# NSE2020_2.net
KiCad netlist of a schematic drawn in EAGLE
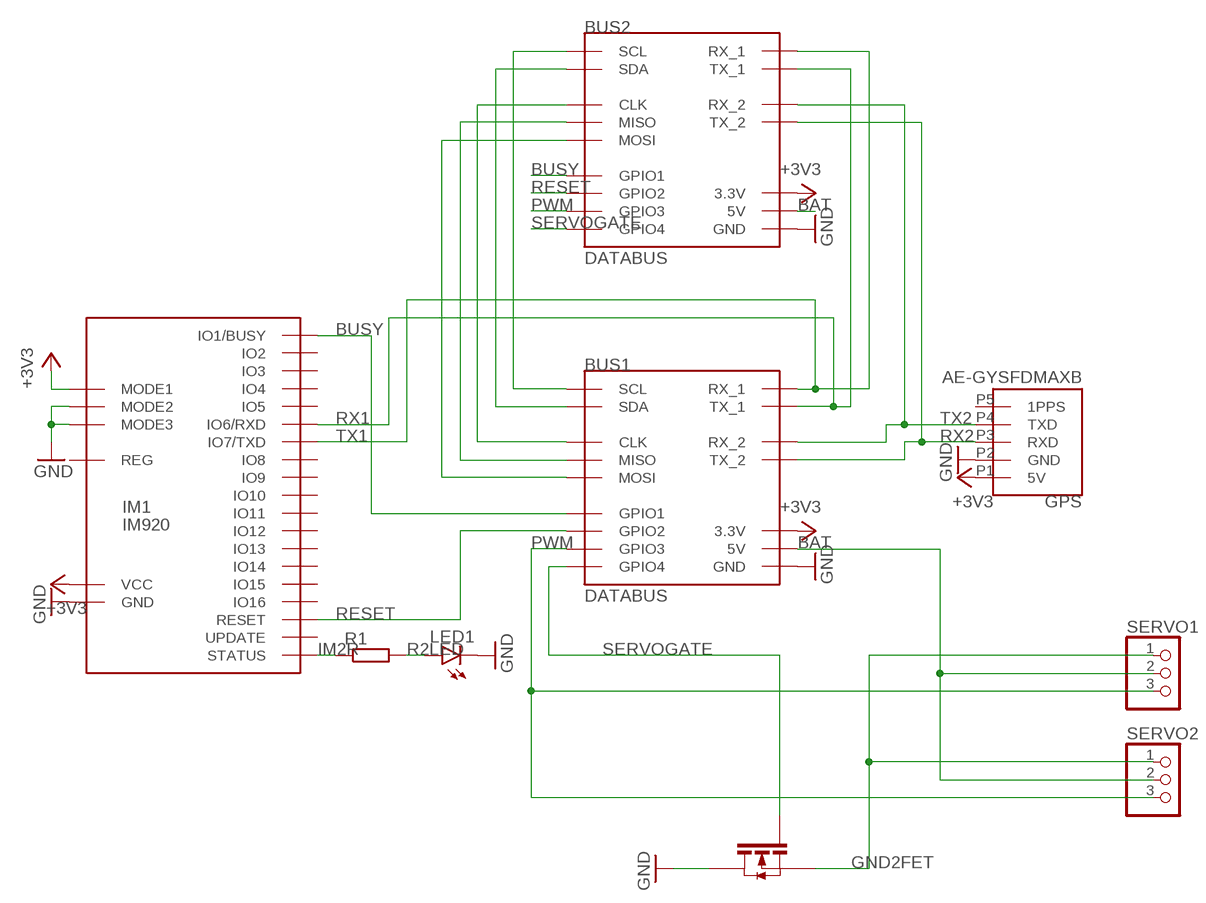
[diagram p0: schematic, sheet 1]

(export (version "E")
  (design (tool "Eeschema 10.0.6"))
  (components
    (comp (ref "BUS1")
      (value "DATABUS")
      (footprint "eagle-import:8X2")
      (libsource (lib "eagle-import") (part "DATABUS"))
    )
    (comp (ref "BUS2")
      (value "DATABUS")
      (footprint "eagle-import:8X2")
      (libsource (lib "eagle-import") (part "DATABUS"))
    )
    (comp (ref "FET1")
      (value "2SK4033")
      (footprint "eagle-import:2SK4033")
      (libsource (lib "eagle-import") (part "2SK4033"))
    )
    (comp (ref "GPS")
      (value "AE-GYSFDMAXB")
      (footprint "eagle-import:AE-GYSFDMAXB")
      (libsource (lib "eagle-import") (part "AE-GYSFDMAXB"))
    )
    (comp (ref "IM1")
      (value "IM920")
      (footprint "eagle-import:IM920")
      (libsource (lib "eagle-import") (part "IM920"))
    )
    (comp (ref "LED1")
      (value "LEDSMT1206")
      (footprint "eagle-import:1206")
      (libsource (lib "eagle-import") (part "LEDSMT1206"))
    )
    (comp (ref "R1")
      (value "R-EU_M2012")
      (footprint "eagle-import:M2012")
      (libsource (lib "eagle-import") (part "R-EU_M2012"))
    )
    (comp (ref "SERVO1")
      (value "PINHD-1X3")
      (footprint "eagle-import:1X03")
      (libsource (lib "eagle-import") (part "PINHD-1X3"))
    )
    (comp (ref "SERVO2")
      (value "PINHD-1X3")
      (footprint "eagle-import:1X03")
      (libsource (lib "eagle-import") (part "PINHD-1X3"))
    )
  )
  (nets
    (net (code "1") (name "+3V3") (class "Default")
      (node (ref "BUS1") (pin "P6") (pinfunction "3.3V_P6") (pintype "bidirectional"))
      (node (ref "BUS2") (pin "P6") (pinfunction "3.3V_P6") (pintype "bidirectional"))
      (node (ref "GPS") (pin "P1") (pinfunction "5V_P1") (pintype "bidirectional"))
      (node (ref "IM1") (pin "IO2") (pinfunction "VCC_IO2") (pintype "bidirectional"))
      (node (ref "IM1") (pin "IO5") (pinfunction "MODE1_IO5") (pintype "bidirectional"))
    )
    (net (code "2") (name "/BAT") (class "Default")
      (node (ref "BUS1") (pin "P7") (pinfunction "5V_P7") (pintype "bidirectional"))
      (node (ref "BUS2") (pin "P7") (pinfunction "5V_P7") (pintype "bidirectional"))
      (node (ref "SERVO1") (pin "2") (pinfunction "2_2") (pintype "passive"))
      (node (ref "SERVO2") (pin "2") (pinfunction "2_2") (pintype "passive"))
    )
    (net (code "3") (name "/BUSY") (class "Default")
      (node (ref "BUS1") (pin "P3") (pinfunction "GPIO1_P3") (pintype "bidirectional"))
      (node (ref "BUS2") (pin "P3") (pinfunction "GPIO1_P3") (pintype "bidirectional"))
      (node (ref "IM1") (pin "IO13") (pinfunction "IO1/BUSY_IO13") (pintype "bidirectional"))
    )
    (net (code "4") (name "/GND2FET") (class "Default")
      (node (ref "FET1") (pin "P$4") (pinfunction "S_P$4") (pintype "bidirectional"))
      (node (ref "SERVO1") (pin "1") (pinfunction "1_1") (pintype "passive"))
      (node (ref "SERVO2") (pin "1") (pinfunction "1_1") (pintype "passive"))
    )
    (net (code "5") (name "/IM2R") (class "Default")
      (node (ref "IM1") (pin "IO3") (pinfunction "STATUS_IO3") (pintype "bidirectional"))
      (node (ref "R1") (pin "1") (pinfunction "1_1") (pintype "passive"))
    )
    (net (code "6") (name "/PWM") (class "Default")
      (node (ref "BUS1") (pin "P14") (pinfunction "GPIO3_P14") (pintype "bidirectional"))
      (node (ref "BUS2") (pin "P14") (pinfunction "GPIO3_P14") (pintype "bidirectional"))
      (node (ref "SERVO1") (pin "3") (pinfunction "3_3") (pintype "passive"))
      (node (ref "SERVO2") (pin "3") (pinfunction "3_3") (pintype "passive"))
    )
    (net (code "7") (name "/R2LED") (class "Default")
      (node (ref "LED1") (pin "A") (pinfunction "A_A") (pintype "passive"))
      (node (ref "R1") (pin "2") (pinfunction "2_2") (pintype "passive"))
    )
    (net (code "8") (name "/RESET") (class "Default")
      (node (ref "BUS1") (pin "P10") (pinfunction "GPIO2_P10") (pintype "bidirectional"))
      (node (ref "BUS2") (pin "P10") (pinfunction "GPIO2_P10") (pintype "bidirectional"))
      (node (ref "IM1") (pin "IO1") (pinfunction "RESET_IO1") (pintype "bidirectional"))
    )
    (net (code "9") (name "/RX1") (class "Default")
      (node (ref "BUS1") (pin "P5") (pinfunction "TX_1_P5") (pintype "bidirectional"))
      (node (ref "BUS2") (pin "P5") (pinfunction "TX_1_P5") (pintype "bidirectional"))
      (node (ref "IM1") (pin "IO16") (pinfunction "IO6/RXD_IO16") (pintype "bidirectional"))
    )
    (net (code "10") (name "/RX2") (class "Default")
      (node (ref "BUS1") (pin "P8") (pinfunction "TX_2_P8") (pintype "bidirectional"))
      (node (ref "BUS2") (pin "P8") (pinfunction "TX_2_P8") (pintype "bidirectional"))
      (node (ref "GPS") (pin "P3") (pinfunction "RXD_P3") (pintype "bidirectional"))
    )
    (net (code "11") (name "/SERVOGATE") (class "Default")
      (node (ref "BUS1") (pin "P15") (pinfunction "GPIO4_P15") (pintype "bidirectional"))
      (node (ref "BUS2") (pin "P15") (pinfunction "GPIO4_P15") (pintype "bidirectional"))
      (node (ref "FET1") (pin "P$3") (pinfunction "G_P$3") (pintype "bidirectional"))
    )
    (net (code "12") (name "/TX1") (class "Default")
      (node (ref "BUS1") (pin "P4") (pinfunction "RX_1_P4") (pintype "bidirectional"))
      (node (ref "BUS2") (pin "P4") (pinfunction "RX_1_P4") (pintype "bidirectional"))
      (node (ref "IM1") (pin "IO10") (pinfunction "IO7/TXD_IO10") (pintype "bidirectional"))
    )
    (net (code "13") (name "/TX2") (class "Default")
      (node (ref "BUS1") (pin "P9") (pinfunction "RX_2_P9") (pintype "bidirectional"))
      (node (ref "BUS2") (pin "P9") (pinfunction "RX_2_P9") (pintype "bidirectional"))
      (node (ref "GPS") (pin "P4") (pinfunction "TXD_P4") (pintype "bidirectional"))
    )
    (net (code "14") (name "GND") (class "Default")
      (node (ref "BUS1") (pin "P11") (pinfunction "GND_P11") (pintype "bidirectional"))
      (node (ref "BUS2") (pin "P11") (pinfunction "GND_P11") (pintype "bidirectional"))
      (node (ref "FET1") (pin "P$1") (pinfunction "D_P$1") (pintype "bidirectional"))
      (node (ref "FET1") (pin "P$2") (pinfunction "D_P$2") (pintype "bidirectional"))
      (node (ref "GPS") (pin "P2") (pinfunction "GND_P2") (pintype "bidirectional"))
      (node (ref "IM1") (pin "IO22") (pinfunction "MODE2_IO22") (pintype "bidirectional"))
      (node (ref "IM1") (pin "IO25") (pinfunction "GND_IO25") (pintype "bidirectional"))
      (node (ref "IM1") (pin "IO4") (pinfunction "MODE3_IO4") (pintype "bidirectional"))
      (node (ref "LED1") (pin "C") (pinfunction "C_C") (pintype "passive"))
    )
    (net (code "15") (name "Net-(BUS1-CLK)") (class "Default")
      (node (ref "BUS1") (pin "P1") (pinfunction "CLK_P1") (pintype "bidirectional"))
      (node (ref "BUS2") (pin "P1") (pinfunction "CLK_P1") (pintype "bidirectional"))
    )
    (net (code "16") (name "Net-(BUS1-MISO)") (class "Default")
      (node (ref "BUS1") (pin "P12") (pinfunction "MISO_P12") (pintype "bidirectional"))
      (node (ref "BUS2") (pin "P12") (pinfunction "MISO_P12") (pintype "bidirectional"))
    )
    (net (code "17") (name "Net-(BUS1-MOSI)") (class "Default")
      (node (ref "BUS1") (pin "P2") (pinfunction "MOSI_P2") (pintype "bidirectional"))
      (node (ref "BUS2") (pin "P2") (pinfunction "MOSI_P2") (pintype "bidirectional"))
    )
    (net (code "18") (name "Net-(BUS1-SCL)") (class "Default")
      (node (ref "BUS1") (pin "P0") (pinfunction "SCL_P0") (pintype "bidirectional"))
      (node (ref "BUS2") (pin "P0") (pinfunction "SCL_P0") (pintype "bidirectional"))
    )
    (net (code "19") (name "Net-(BUS1-SDA)") (class "Default")
      (node (ref "BUS1") (pin "P13") (pinfunction "SDA_P13") (pintype "bidirectional"))
      (node (ref "BUS2") (pin "P13") (pinfunction "SDA_P13") (pintype "bidirectional"))
    )
    (net (code "20") (name "unconnected-(GPS-1PPS-PadP5)") (class "Default")
      (node (ref "GPS") (pin "P5") (pinfunction "1PPS_P5") (pintype "bidirectional"))
    )
    (net (code "21") (name "unconnected-(IM1-IO2-PadIO14)") (class "Default")
      (node (ref "IM1") (pin "IO14") (pinfunction "IO2_IO14") (pintype "bidirectional"))
    )
    (net (code "22") (name "unconnected-(IM1-IO3-PadIO12)") (class "Default")
      (node (ref "IM1") (pin "IO12") (pinfunction "IO3_IO12") (pintype "bidirectional"))
    )
    (net (code "23") (name "unconnected-(IM1-IO4-PadIO15)") (class "Default")
      (node (ref "IM1") (pin "IO15") (pinfunction "IO4_IO15") (pintype "bidirectional"))
    )
    (net (code "24") (name "unconnected-(IM1-IO5-PadIO11)") (class "Default")
      (node (ref "IM1") (pin "IO11") (pinfunction "IO5_IO11") (pintype "bidirectional"))
    )
    (net (code "25") (name "unconnected-(IM1-IO8-PadIO17)") (class "Default")
      (node (ref "IM1") (pin "IO17") (pinfunction "IO8_IO17") (pintype "bidirectional"))
    )
    (net (code "26") (name "unconnected-(IM1-IO10-PadIO18)") (class "Default")
      (node (ref "IM1") (pin "IO18") (pinfunction "IO10_IO18") (pintype "bidirectional"))
    )
    (net (code "27") (name "unconnected-(IM1-IO11-PadIO8)") (class "Default")
      (node (ref "IM1") (pin "IO8") (pinfunction "IO11_IO8") (pintype "bidirectional"))
    )
    (net (code "28") (name "unconnected-(IM1-IO12-PadIO19)") (class "Default")
      (node (ref "IM1") (pin "IO19") (pinfunction "IO12_IO19") (pintype "bidirectional"))
    )
    (net (code "29") (name "unconnected-(IM1-IO13-PadIO7)") (class "Default")
      (node (ref "IM1") (pin "IO7") (pinfunction "IO13_IO7") (pintype "bidirectional"))
    )
    (net (code "30") (name "unconnected-(IM1-IO14-PadIO20)") (class "Default")
      (node (ref "IM1") (pin "IO20") (pinfunction "IO14_IO20") (pintype "bidirectional"))
    )
    (net (code "31") (name "unconnected-(IM1-IO15-PadIO6)") (class "Default")
      (node (ref "IM1") (pin "IO6") (pinfunction "IO15_IO6") (pintype "bidirectional"))
    )
    (net (code "32") (name "unconnected-(IM1-IO16-PadIO21)") (class "Default")
      (node (ref "IM1") (pin "IO21") (pinfunction "IO16_IO21") (pintype "bidirectional"))
    )
    (net (code "33") (name "unconnected-(IM1-PadIO9)") (class "Default")
      (node (ref "IM1") (pin "IO9") (pinfunction "IO9_IO9") (pintype "bidirectional"))
    )
    (net (code "34") (name "unconnected-(IM1-REG-PadIO24)") (class "Default")
      (node (ref "IM1") (pin "IO24") (pinfunction "REG_IO24") (pintype "bidirectional"))
    )
    (net (code "35") (name "unconnected-(IM1-UPDATE-PadIO23)") (class "Default")
      (node (ref "IM1") (pin "IO23") (pinfunction "UPDATE_IO23") (pintype "bidirectional"))
    )
  )
)
